# mapleCUx_large_085-MAPLE-unten.net
KiCad netlist of a schematic drawn in EAGLE
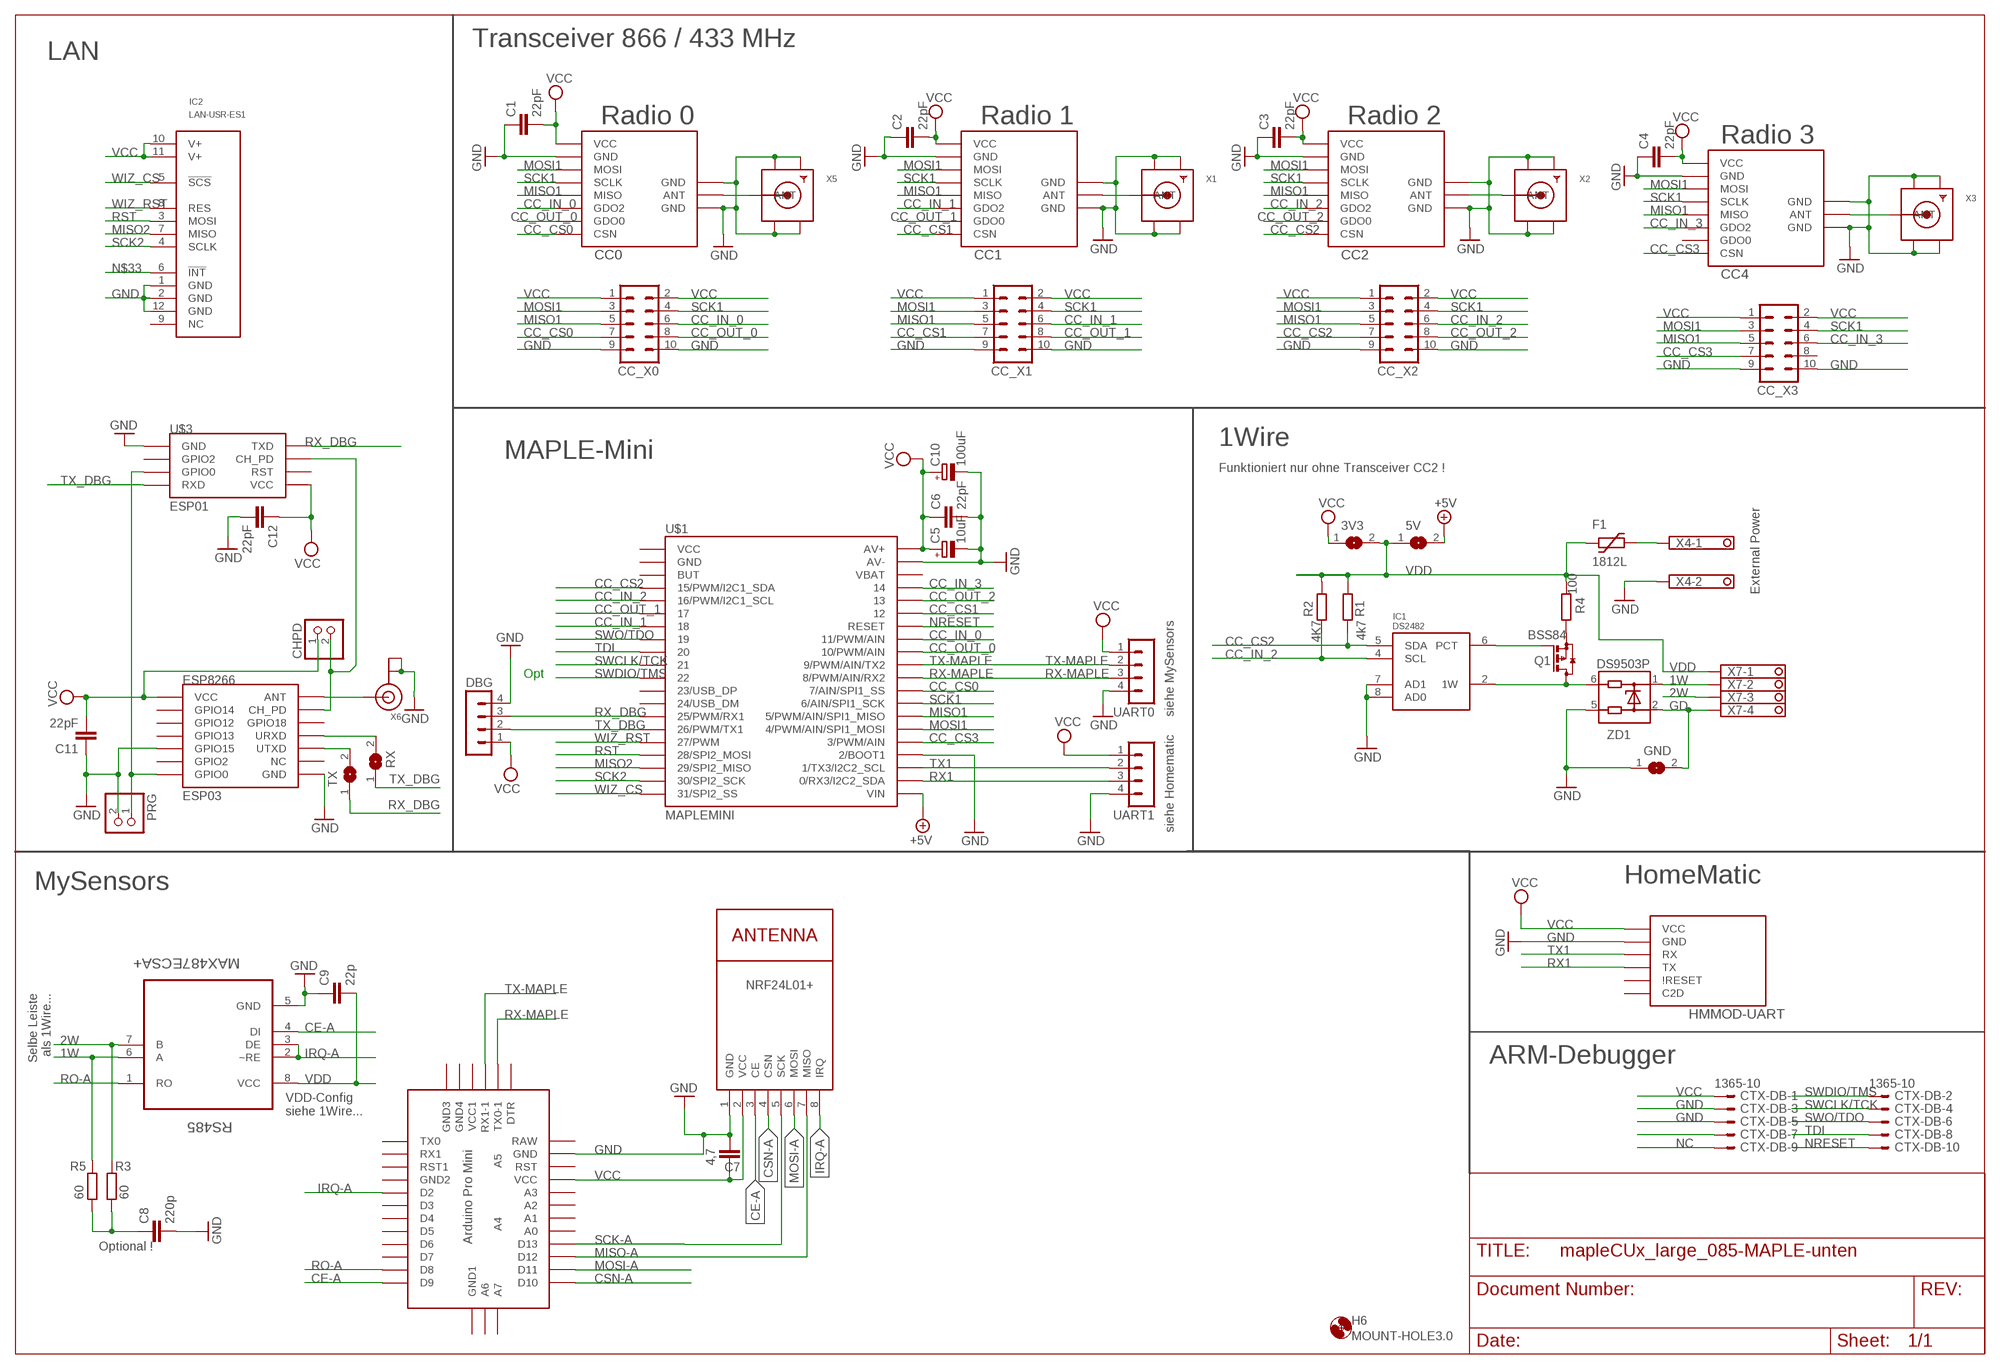
[diagram p0: schematic, sheet 1]

(export (version "E")
  (design (tool "Eeschema 10.0.6"))
  (components
    (comp (ref "3V3") (value "SJ") (footprint "eagle-import:SJ") (libsource (lib "eagle-import") (part "SJ")))
    (comp (ref "5V") (value "SJ") (footprint "eagle-import:SJ") (libsource (lib "eagle-import") (part "SJ")))
    (comp (ref "C1")
      (value "22pF")
      (footprint "eagle-import:C0805")
      (libsource (lib "eagle-import") (part "C-EUC0805"))
    )
    (comp (ref "C2")
      (value "22pF")
      (footprint "eagle-import:C0805")
      (libsource (lib "eagle-import") (part "C-EUC0805"))
    )
    (comp (ref "C3")
      (value "22pF")
      (footprint "eagle-import:C0805")
      (libsource (lib "eagle-import") (part "C-EUC0805"))
    )
    (comp (ref "C4")
      (value "22pF")
      (footprint "eagle-import:C0805")
      (libsource (lib "eagle-import") (part "C-EUC0805"))
    )
    (comp (ref "C5")
      (value "10uF")
      (footprint "eagle-import:R_2012-12W")
      (libsource (lib "eagle-import") (part "CPOL-EUR/2012-12W"))
    )
    (comp (ref "C6")
      (value "22pF")
      (footprint "eagle-import:C0805")
      (libsource (lib "eagle-import") (part "C-EUC0805"))
    )
    (comp (ref "C7")
      (value "4,7")
      (footprint "eagle-import:C1210")
      (libsource (lib "eagle-import") (part "C-EUC1210"))
    )
    (comp (ref "C8")
      (value "220p")
      (footprint "eagle-import:C0805")
      (libsource (lib "eagle-import") (part "C-EUC0805"))
    )
    (comp (ref "C9")
      (value "22p")
      (footprint "eagle-import:C0805")
      (libsource (lib "eagle-import") (part "C-EUC0805"))
    )
    (comp (ref "C10")
      (value "100uF")
      (footprint "eagle-import:E5-8,5")
      (libsource (lib "eagle-import") (part "CPOL-EUE5-8.5"))
    )
    (comp (ref "C11")
      (value "22pF")
      (footprint "eagle-import:C0805")
      (libsource (lib "eagle-import") (part "C-EUC0805"))
    )
    (comp (ref "C12")
      (value "22pF")
      (footprint "eagle-import:C0805")
      (libsource (lib "eagle-import") (part "C-EUC0805"))
    )
    (comp (ref "CC0")
      (value "CC1101")
      (footprint "eagle-import:CC1101_MODULE1_SMD")
      (libsource (lib "eagle-import") (part "CC1101_MODULE1SMD"))
    )
    (comp (ref "CC1")
      (value "CC1101_MODULE1SMD")
      (footprint "eagle-import:CC1101_MODULE1_SMD")
      (libsource (lib "eagle-import") (part "CC1101_MODULE1SMD"))
    )
    (comp (ref "CC2")
      (value "CC1101_MODULE1SMD")
      (footprint "eagle-import:CC1101_MODULE1_SMD")
      (libsource (lib "eagle-import") (part "CC1101_MODULE1SMD"))
    )
    (comp (ref "CC4")
      (value "CC1101_MODULE1SMD")
      (footprint "eagle-import:CC1101_MODULE1_SMD")
      (libsource (lib "eagle-import") (part "CC1101_MODULE1SMD"))
    )
    (comp (ref "CC_X0")
      (value "MA05-2")
      (footprint "eagle-import:MA05-2")
      (libsource (lib "eagle-import") (part "MA05-2"))
    )
    (comp (ref "CC_X1")
      (value "MA05-2")
      (footprint "eagle-import:MA05-2")
      (libsource (lib "eagle-import") (part "MA05-2"))
    )
    (comp (ref "CC_X2")
      (value "MA05-2")
      (footprint "eagle-import:MA05-2")
      (libsource (lib "eagle-import") (part "MA05-2"))
    )
    (comp (ref "CC_X3")
      (value "MA05-2")
      (footprint "eagle-import:MA05-2")
      (libsource (lib "eagle-import") (part "MA05-2"))
    )
    (comp (ref "CHPD")
      (value "PINHD-1X2")
      (footprint "eagle-import:1X02")
      (libsource (lib "eagle-import") (part "PINHD-1X2"))
    )
    (comp (ref "CTX-DB")
      (value "1365-10")
      (footprint "eagle-import:1365-10")
      (libsource (lib "eagle-import") (part "1365-10"))
    )
    (comp (ref "DBG")
      (value "MA04-1")
      (footprint "eagle-import:MA04-1")
      (libsource (lib "eagle-import") (part "MA04-1"))
    )
    (comp (ref "ESP8266")
      (value "ESP03")
      (footprint "eagle-import:ESP03")
      (libsource (lib "eagle-import") (part "ESP03"))
    )
    (comp (ref "F1")
      (value "1812L")
      (footprint "eagle-import:1812L")
      (libsource (lib "eagle-import") (part "1812L"))
    )
    (comp (ref "GND") (value "SJ") (footprint "eagle-import:SJ") (libsource (lib "eagle-import") (part "SJ")))
    (comp (ref "H6")
      (value "MOUNT-HOLE3.0")
      (footprint "eagle-import:3,0")
      (libsource (lib "eagle-import") (part "MOUNT-HOLE3.0"))
    )
    (comp (ref "HMMOD-UART")
      (value "HM-MOD-UARTDIL")
      (footprint "eagle-import:HM-MOD-UART-DIL")
      (libsource (lib "eagle-import") (part "HM-MOD-UARTDIL"))
    )
    (comp (ref "IC1")
      (value "DS2482")
      (footprint "eagle-import:SO08")
      (libsource (lib "eagle-import") (part "DS2482-100S"))
    )
    (comp (ref "IC2")
      (value "LAN-USR-ES1")
      (footprint "eagle-import:USR-ES1")
      (libsource (lib "eagle-import") (part "LAN-USR-ES1"))
    )
    (comp (ref "NRF24L01+")
      (value "NRF24L01+")
      (footprint "eagle-import:WIRELESS-NRF24L01")
      (libsource (lib "eagle-import") (part "WIRELESS-NRF24L01"))
    )
    (comp (ref "PRG")
      (value "PINHD-1X2")
      (footprint "eagle-import:1X02")
      (libsource (lib "eagle-import") (part "PINHD-1X2"))
    )
    (comp (ref "Q1")
      (value "BSS84")
      (footprint "eagle-import:SOT23")
      (libsource (lib "eagle-import") (part "BSS84"))
    )
    (comp (ref "R1")
      (value "4k7")
      (footprint "eagle-import:R0805")
      (libsource (lib "eagle-import") (part "R-EU_R0805"))
    )
    (comp (ref "R2")
      (value "4K7")
      (footprint "eagle-import:R0805")
      (libsource (lib "eagle-import") (part "R-EU_R0805"))
    )
    (comp (ref "R3")
      (value "60")
      (footprint "eagle-import:R0805")
      (libsource (lib "eagle-import") (part "R-EU_R0805"))
    )
    (comp (ref "R4")
      (value "100")
      (footprint "eagle-import:R0805")
      (libsource (lib "eagle-import") (part "R-EU_R0805"))
    )
    (comp (ref "R5")
      (value "60")
      (footprint "eagle-import:R0805")
      (libsource (lib "eagle-import") (part "R-EU_R0805"))
    )
    (comp (ref "RS485")
      (value "MAX487ECSA+")
      (footprint "eagle-import:SOIC127P600X175-8N")
      (libsource (lib "eagle-import") (part "MAX487ECSA+"))
    )
    (comp (ref "RX") (value "SJ") (footprint "eagle-import:SJ") (libsource (lib "eagle-import") (part "SJ")))
    (comp (ref "TX") (value "SJ") (footprint "eagle-import:SJ") (libsource (lib "eagle-import") (part "SJ")))
    (comp (ref "U$1")
      (value "MAPLEMINI")
      (footprint "eagle-import:20-DIP")
      (libsource (lib "eagle-import") (part "MAPLEMINI"))
    )
    (comp (ref "U$2")
      (value "ABK-PRO-MINI")
      (footprint "eagle-import:ABK-PRO-MINI")
      (libsource (lib "eagle-import") (part "ABK-PRO-MINI"))
    )
    (comp (ref "U$3")
      (value "ESP01")
      (footprint "eagle-import:ESP01")
      (libsource (lib "eagle-import") (part "ESP01"))
    )
    (comp (ref "UART0")
      (value "MA04-1")
      (footprint "eagle-import:MA04-1")
      (libsource (lib "eagle-import") (part "MA04-1"))
    )
    (comp (ref "UART1")
      (value "MA04-1")
      (footprint "eagle-import:MA04-1")
      (libsource (lib "eagle-import") (part "MA04-1"))
    )
    (comp (ref "X1")
      (value "SMACONNECTOR_EDGE_UFL")
      (footprint "eagle-import:SMA_EDGELAUNCH_UFL")
      (libsource (lib "eagle-import") (part "SMACONNECTOR_EDGE_UFL"))
    )
    (comp (ref "X2")
      (value "SMACONNECTOR_EDGE_UFL")
      (footprint "eagle-import:SMA_EDGELAUNCH_UFL")
      (libsource (lib "eagle-import") (part "SMACONNECTOR_EDGE_UFL"))
    )
    (comp (ref "X3")
      (value "SMACONNECTOR_EDGE_UFL")
      (footprint "eagle-import:SMA_EDGELAUNCH_UFL")
      (libsource (lib "eagle-import") (part "SMACONNECTOR_EDGE_UFL"))
    )
    (comp (ref "X4")
      (value "1751248")
      (footprint "eagle-import:1751248")
      (libsource (lib "eagle-import") (part "1751248"))
    )
    (comp (ref "X5")
      (value "SMACONNECTOR_EDGE_UFL")
      (footprint "eagle-import:SMA_EDGELAUNCH_UFL")
      (libsource (lib "eagle-import") (part "SMACONNECTOR_EDGE_UFL"))
    )
    (comp (ref "X6")
      (value "ANTENNA_U.FL")
      (footprint "eagle-import:U.FL")
      (libsource (lib "eagle-import") (part "ANTENNA_U.FL"))
    )
    (comp (ref "X7")
      (value "1751264")
      (footprint "eagle-import:1751264")
      (libsource (lib "eagle-import") (part "1751264"))
    )
    (comp (ref "ZD1")
      (value "DS9503P")
      (footprint "eagle-import:TSOC6")
      (libsource (lib "eagle-import") (part "DS9503P"))
    )
  )
  (nets
    (net (code "1") (name "+5V") (class "Default")
      (node (ref "5V") (pin "2") (pinfunction "2_2") (pintype "passive"))
      (node (ref "U$1") (pin "21") (pinfunction "VIN_21") (pintype "bidirectional"))
    )
    (net (code "2") (name "/1W") (class "Default")
      (node (ref "R5") (pin "2") (pinfunction "2_2") (pintype "passive"))
      (node (ref "RS485") (pin "6") (pinfunction "A_6") (pintype "bidirectional"))
      (node (ref "X7") (pin "2") (pinfunction "K_2") (pintype "passive"))
      (node (ref "ZD1") (pin "1") (pinfunction "P$1_1") (pintype "passive"))
    )
    (net (code "3") (name "/2W") (class "Default")
      (node (ref "R3") (pin "2") (pinfunction "2_2") (pintype "passive"))
      (node (ref "RS485") (pin "7") (pinfunction "B_7") (pintype "bidirectional"))
      (node (ref "X7") (pin "3") (pinfunction "K_3") (pintype "passive"))
    )
    (net (code "4") (name "/CC_CS0") (class "Default")
      (node (ref "CC0") (pin "CSN") (pinfunction "CSN_CSN") (pintype "bidirectional"))
      (node (ref "CC_X0") (pin "7") (pinfunction "7_7") (pintype "passive"))
      (node (ref "U$1") (pin "29") (pinfunction "7/AIN/SPI1_SS_29") (pintype "bidirectional"))
    )
    (net (code "5") (name "/CC_CS1") (class "Default")
      (node (ref "CC1") (pin "CSN") (pinfunction "CSN_CSN") (pintype "bidirectional"))
      (node (ref "CC_X1") (pin "7") (pinfunction "7_7") (pintype "passive"))
      (node (ref "U$1") (pin "35") (pinfunction "12_35") (pintype "bidirectional"))
    )
    (net (code "6") (name "/CC_CS2") (class "Default")
      (node (ref "CC2") (pin "CSN") (pinfunction "CSN_CSN") (pintype "bidirectional"))
      (node (ref "CC_X2") (pin "7") (pinfunction "7_7") (pintype "passive"))
      (node (ref "IC1") (pin "5") (pinfunction "SDA_5") (pintype "bidirectional"))
      (node (ref "R1") (pin "2") (pinfunction "2_2") (pintype "passive"))
      (node (ref "U$1") (pin "4") (pinfunction "15/PWM/I2C1_SDA_4") (pintype "bidirectional"))
    )
    (net (code "7") (name "/CC_CS3") (class "Default")
      (node (ref "CC4") (pin "CSN") (pinfunction "CSN_CSN") (pintype "bidirectional"))
      (node (ref "CC_X3") (pin "7") (pinfunction "7_7") (pintype "passive"))
      (node (ref "U$1") (pin "25") (pinfunction "3/PWM/AIN_25") (pintype "bidirectional"))
    )
    (net (code "8") (name "/CC_IN_0") (class "Default")
      (node (ref "CC0") (pin "GDO2") (pinfunction "GDO2_GDO2") (pintype "bidirectional"))
      (node (ref "CC_X0") (pin "6") (pinfunction "6_6") (pintype "passive"))
      (node (ref "U$1") (pin "33") (pinfunction "11/PWM/AIN_33") (pintype "bidirectional"))
    )
    (net (code "9") (name "/CC_IN_1") (class "Default")
      (node (ref "CC1") (pin "GDO2") (pinfunction "GDO2_GDO2") (pintype "bidirectional"))
      (node (ref "CC_X1") (pin "6") (pinfunction "6_6") (pintype "passive"))
      (node (ref "U$1") (pin "7") (pinfunction "18_7") (pintype "bidirectional"))
    )
    (net (code "10") (name "/CC_IN_2") (class "Default")
      (node (ref "CC2") (pin "GDO2") (pinfunction "GDO2_GDO2") (pintype "bidirectional"))
      (node (ref "CC_X2") (pin "6") (pinfunction "6_6") (pintype "passive"))
      (node (ref "IC1") (pin "4") (pinfunction "SCL_4") (pintype "input"))
      (node (ref "R2") (pin "2") (pinfunction "2_2") (pintype "passive"))
      (node (ref "U$1") (pin "5") (pinfunction "16/PWM/I2C1_SCL_5") (pintype "bidirectional"))
    )
    (net (code "11") (name "/CC_IN_3") (class "Default")
      (node (ref "CC4") (pin "GDO2") (pinfunction "GDO2_GDO2") (pintype "bidirectional"))
      (node (ref "CC_X3") (pin "6") (pinfunction "6_6") (pintype "passive"))
      (node (ref "U$1") (pin "37") (pinfunction "14_37") (pintype "bidirectional"))
    )
    (net (code "12") (name "/CC_OUT_0") (class "Default")
      (node (ref "CC0") (pin "GDO0") (pinfunction "GDO0_GDO0") (pintype "bidirectional"))
      (node (ref "CC_X0") (pin "8") (pinfunction "8_8") (pintype "passive"))
      (node (ref "U$1") (pin "32") (pinfunction "10/PWM/AIN_32") (pintype "bidirectional"))
    )
    (net (code "13") (name "/CC_OUT_1") (class "Default")
      (node (ref "CC1") (pin "GDO0") (pinfunction "GDO0_GDO0") (pintype "bidirectional"))
      (node (ref "CC_X1") (pin "8") (pinfunction "8_8") (pintype "passive"))
      (node (ref "U$1") (pin "6") (pinfunction "17_6") (pintype "bidirectional"))
    )
    (net (code "14") (name "/CC_OUT_2") (class "Default")
      (node (ref "CC2") (pin "GDO0") (pinfunction "GDO0_GDO0") (pintype "bidirectional"))
      (node (ref "CC_X2") (pin "8") (pinfunction "8_8") (pintype "passive"))
      (node (ref "U$1") (pin "36") (pinfunction "13_36") (pintype "bidirectional"))
    )
    (net (code "15") (name "/GD") (class "Default")
      (node (ref "GND") (pin "2") (pinfunction "2_2") (pintype "passive"))
      (node (ref "X7") (pin "4") (pinfunction "K_4") (pintype "passive"))
      (node (ref "ZD1") (pin "2") (pinfunction "P$2_2") (pintype "passive"))
    )
    (net (code "16") (name "/MISO-A") (class "Default")
      (node (ref "NRF24L01+") (pin "7") (pinfunction "MISO_7") (pintype "bidirectional"))
      (node (ref "U$2") (pin "D12") (pinfunction "D12_D12") (pintype "bidirectional"))
    )
    (net (code "17") (name "/MISO1") (class "Default")
      (node (ref "CC0") (pin "MISO") (pinfunction "MISO_MISO") (pintype "bidirectional"))
      (node (ref "CC1") (pin "MISO") (pinfunction "MISO_MISO") (pintype "bidirectional"))
      (node (ref "CC2") (pin "MISO") (pinfunction "MISO_MISO") (pintype "bidirectional"))
      (node (ref "CC4") (pin "MISO") (pinfunction "MISO_MISO") (pintype "bidirectional"))
      (node (ref "CC_X0") (pin "5") (pinfunction "5_5") (pintype "passive"))
      (node (ref "CC_X1") (pin "5") (pinfunction "5_5") (pintype "passive"))
      (node (ref "CC_X2") (pin "5") (pinfunction "5_5") (pintype "passive"))
      (node (ref "CC_X3") (pin "5") (pinfunction "5_5") (pintype "passive"))
      (node (ref "U$1") (pin "27") (pinfunction "5/PWM/AIN/SPI1_MISO_27") (pintype "bidirectional"))
    )
    (net (code "18") (name "/MISO2") (class "Default")
      (node (ref "IC2") (pin "7") (pinfunction "MISO_7") (pintype "bidirectional"))
      (node (ref "U$1") (pin "18") (pinfunction "29/SPI2_MISO_18") (pintype "bidirectional"))
    )
    (net (code "19") (name "/MOSI1") (class "Default")
      (node (ref "CC0") (pin "MOSI") (pinfunction "MOSI_MOSI") (pintype "bidirectional"))
      (node (ref "CC1") (pin "MOSI") (pinfunction "MOSI_MOSI") (pintype "bidirectional"))
      (node (ref "CC2") (pin "MOSI") (pinfunction "MOSI_MOSI") (pintype "bidirectional"))
      (node (ref "CC4") (pin "MOSI") (pinfunction "MOSI_MOSI") (pintype "bidirectional"))
      (node (ref "CC_X0") (pin "3") (pinfunction "3_3") (pintype "passive"))
      (node (ref "CC_X1") (pin "3") (pinfunction "3_3") (pintype "passive"))
      (node (ref "CC_X2") (pin "3") (pinfunction "3_3") (pintype "passive"))
      (node (ref "CC_X3") (pin "3") (pinfunction "3_3") (pintype "passive"))
      (node (ref "U$1") (pin "26") (pinfunction "4/PWM/AIN/SPI1_MOSI_26") (pintype "bidirectional"))
    )
    (net (code "20") (name "/N$33") (class "Default")
      (node (ref "IC2") (pin "6") (pinfunction "~{INT}_6") (pintype "output"))
    )
    (net (code "21") (name "/NC") (class "Default")
      (node (ref "CTX-DB") (pin "9") (pinfunction "S_9") (pintype "passive"))
    )
    (net (code "22") (name "/NRESET") (class "Default")
      (node (ref "CTX-DB") (pin "10") (pinfunction "S_10") (pintype "passive"))
      (node (ref "U$1") (pin "34") (pinfunction "RESET_34") (pintype "bidirectional"))
    )
    (net (code "23") (name "/RO-A") (class "Default")
      (node (ref "RS485") (pin "1") (pinfunction "RO_1") (pintype "output"))
      (node (ref "U$2") (pin "D8") (pinfunction "D8_D8") (pintype "bidirectional"))
    )
    (net (code "24") (name "/RST") (class "Default")
      (node (ref "IC2") (pin "3") (pinfunction "MOSI_3") (pintype "bidirectional"))
      (node (ref "U$1") (pin "17") (pinfunction "28/SPI2_MOSI_17") (pintype "bidirectional"))
    )
    (net (code "25") (name "/RX-MAPLE") (class "Default")
      (node (ref "U$1") (pin "30") (pinfunction "8/PWM/AIN/RX2_30") (pintype "bidirectional"))
      (node (ref "U$2") (pin "TX0-1") (pinfunction "TX0-1_TX0-1") (pintype "bidirectional"))
      (node (ref "UART0") (pin "3") (pinfunction "3_3") (pintype "passive"))
    )
    (net (code "26") (name "/RX1") (class "Default")
      (node (ref "HMMOD-UART") (pin "5") (pinfunction "TX_5") (pintype "bidirectional"))
      (node (ref "U$1") (pin "22") (pinfunction "0/RX3/I2C2_SDA_22") (pintype "bidirectional"))
      (node (ref "UART1") (pin "3") (pinfunction "3_3") (pintype "passive"))
    )
    (net (code "27") (name "/RX_DBG") (class "Default")
      (node (ref "DBG") (pin "3") (pinfunction "3_3") (pintype "passive"))
      (node (ref "TX") (pin "1") (pinfunction "1_1") (pintype "passive"))
      (node (ref "U$1") (pin "14") (pinfunction "25/PWM/RX1_14") (pintype "bidirectional"))
      (node (ref "U$3") (pin "TX") (pinfunction "TXD_TX") (pintype "bidirectional"))
    )
    (net (code "28") (name "/SCK-A") (class "Default")
      (node (ref "NRF24L01+") (pin "5") (pinfunction "SCK_5") (pintype "bidirectional"))
      (node (ref "U$2") (pin "D13") (pinfunction "D13_D13") (pintype "bidirectional"))
    )
    (net (code "29") (name "/SCK1") (class "Default")
      (node (ref "CC0") (pin "SCLK") (pinfunction "SCLK_SCLK") (pintype "bidirectional"))
      (node (ref "CC1") (pin "SCLK") (pinfunction "SCLK_SCLK") (pintype "bidirectional"))
      (node (ref "CC2") (pin "SCLK") (pinfunction "SCLK_SCLK") (pintype "bidirectional"))
      (node (ref "CC4") (pin "SCLK") (pinfunction "SCLK_SCLK") (pintype "bidirectional"))
      (node (ref "CC_X0") (pin "4") (pinfunction "4_4") (pintype "passive"))
      (node (ref "CC_X1") (pin "4") (pinfunction "4_4") (pintype "passive"))
      (node (ref "CC_X2") (pin "4") (pinfunction "4_4") (pintype "passive"))
      (node (ref "CC_X3") (pin "4") (pinfunction "4_4") (pintype "passive"))
      (node (ref "U$1") (pin "28") (pinfunction "6/AIN/SPI1_SCK_28") (pintype "bidirectional"))
    )
    (net (code "30") (name "/SCK2") (class "Default")
      (node (ref "IC2") (pin "4") (pinfunction "SCLK_4") (pintype "input"))
      (node (ref "U$1") (pin "19") (pinfunction "30/SPI2_SCK_19") (pintype "bidirectional"))
    )
    (net (code "31") (name "/SWCLK{slash}TCK") (class "Default")
      (node (ref "CTX-DB") (pin "4") (pinfunction "S_4") (pintype "passive"))
      (node (ref "U$1") (pin "10") (pinfunction "21_10") (pintype "bidirectional"))
    )
    (net (code "32") (name "/SWDIO{slash}TMS") (class "Default")
      (node (ref "CTX-DB") (pin "2") (pinfunction "S_2") (pintype "passive"))
      (node (ref "U$1") (pin "11") (pinfunction "22_11") (pintype "bidirectional"))
    )
    (net (code "33") (name "/SWO{slash}TDO") (class "Default")
      (node (ref "CTX-DB") (pin "6") (pinfunction "S_6") (pintype "passive"))
      (node (ref "U$1") (pin "8") (pinfunction "19_8") (pintype "bidirectional"))
    )
    (net (code "34") (name "/TDI") (class "Default")
      (node (ref "CTX-DB") (pin "8") (pinfunction "S_8") (pintype "passive"))
      (node (ref "U$1") (pin "9") (pinfunction "20_9") (pintype "bidirectional"))
    )
    (net (code "35") (name "/TX-MAPLE") (class "Default")
      (node (ref "U$1") (pin "31") (pinfunction "9/PWM/AIN/TX2_31") (pintype "bidirectional"))
      (node (ref "U$2") (pin "RX1-1") (pinfunction "RX1-1_RX1-1") (pintype "bidirectional"))
      (node (ref "UART0") (pin "2") (pinfunction "2_2") (pintype "passive"))
    )
    (net (code "36") (name "/TX1") (class "Default")
      (node (ref "HMMOD-UART") (pin "6") (pinfunction "RX_6") (pintype "bidirectional"))
      (node (ref "U$1") (pin "23") (pinfunction "1/TX3/I2C2_SCL_23") (pintype "bidirectional"))
      (node (ref "UART1") (pin "2") (pinfunction "2_2") (pintype "passive"))
    )
    (net (code "37") (name "/TX_DBG") (class "Default")
      (node (ref "DBG") (pin "2") (pinfunction "2_2") (pintype "passive"))
      (node (ref "RX") (pin "1") (pinfunction "1_1") (pintype "passive"))
      (node (ref "U$1") (pin "15") (pinfunction "26/PWM/TX1_15") (pintype "bidirectional"))
      (node (ref "U$3") (pin "RX") (pinfunction "RXD_RX") (pintype "bidirectional"))
    )
    (net (code "38") (name "/VDD") (class "Default")
      (node (ref "3V3") (pin "2") (pinfunction "2_2") (pintype "passive"))
      (node (ref "5V") (pin "1") (pinfunction "1_1") (pintype "passive"))
      (node (ref "C9") (pin "2") (pinfunction "2_2") (pintype "passive"))
      (node (ref "F1") (pin "P$1") (pinfunction "1_P$1") (pintype "passive"))
      (node (ref "R1") (pin "1") (pinfunction "1_1") (pintype "passive"))
      (node (ref "R2") (pin "1") (pinfunction "1_1") (pintype "passive"))
      (node (ref "R4") (pin "2") (pinfunction "2_2") (pintype "passive"))
      (node (ref "RS485") (pin "8") (pinfunction "VCC_8") (pintype "power_in"))
      (node (ref "X7") (pin "1") (pinfunction "K_1") (pintype "passive"))
    )
    (net (code "39") (name "/WIZ_CS") (class "Default")
      (node (ref "IC2") (pin "5") (pinfunction "~{SCS}_5") (pintype "input"))
      (node (ref "U$1") (pin "20") (pinfunction "31/SPI2_SS_20") (pintype "bidirectional"))
    )
    (net (code "40") (name "/WIZ_RST") (class "Default")
      (node (ref "IC2") (pin "8") (pinfunction "RES_8") (pintype "input"))
      (node (ref "U$1") (pin "16") (pinfunction "27/PWM_16") (pintype "bidirectional"))
    )
    (net (code "41") (name "CE-A") (class "Default")
      (node (ref "NRF24L01+") (pin "3") (pinfunction "CE_3") (pintype "bidirectional"))
      (node (ref "RS485") (pin "4") (pinfunction "DI_4") (pintype "input"))
      (node (ref "U$2") (pin "D9") (pinfunction "D9_D9") (pintype "bidirectional"))
    )
    (net (code "42") (name "CSN-A") (class "Default")
      (node (ref "NRF24L01+") (pin "4") (pinfunction "CSN_4") (pintype "bidirectional"))
      (node (ref "U$2") (pin "D10") (pinfunction "D10_D10") (pintype "bidirectional"))
    )
    (net (code "43") (name "GND") (class "Default")
      (node (ref "C1") (pin "1") (pinfunction "1_1") (pintype "passive"))
      (node (ref "C10") (pin "-") (pinfunction "-_-") (pintype "passive"))
      (node (ref "C11") (pin "1") (pinfunction "1_1") (pintype "passive"))
      (node (ref "C12") (pin "2") (pinfunction "2_2") (pintype "passive"))
      (node (ref "C2") (pin "1") (pinfunction "1_1") (pintype "passive"))
      (node (ref "C3") (pin "1") (pinfunction "1_1") (pintype "passive"))
      (node (ref "C4") (pin "1") (pinfunction "1_1") (pintype "passive"))
      (node (ref "C5") (pin "-") (pinfunction "-_-") (pintype "passive"))
      (node (ref "C6") (pin "2") (pinfunction "2_2") (pintype "passive"))
      (node (ref "C7") (pin "1") (pinfunction "1_1") (pintype "passive"))
      (node (ref "C8") (pin "2") (pinfunction "2_2") (pintype "passive"))
      (node (ref "C9") (pin "1") (pinfunction "1_1") (pintype "passive"))
      (node (ref "CC0") (pin "GND@0") (pinfunction "GND_GND@0") (pintype "power_in"))
      (node (ref "CC0") (pin "GND@1") (pinfunction "GND_GND@1") (pintype "power_in"))
      (node (ref "CC0") (pin "GND@2") (pinfunction "GND_GND@2") (pintype "power_in"))
      (node (ref "CC1") (pin "GND@0") (pinfunction "GND_GND@0") (pintype "power_in"))
      (node (ref "CC1") (pin "GND@1") (pinfunction "GND_GND@1") (pintype "power_in"))
      (node (ref "CC1") (pin "GND@2") (pinfunction "GND_GND@2") (pintype "power_in"))
      (node (ref "CC2") (pin "GND@0") (pinfunction "GND_GND@0") (pintype "power_in"))
      (node (ref "CC2") (pin "GND@1") (pinfunction "GND_GND@1") (pintype "power_in"))
      (node (ref "CC2") (pin "GND@2") (pinfunction "GND_GND@2") (pintype "power_in"))
      (node (ref "CC4") (pin "GND@0") (pinfunction "GND_GND@0") (pintype "power_in"))
      (node (ref "CC4") (pin "GND@1") (pinfunction "GND_GND@1") (pintype "power_in"))
      (node (ref "CC4") (pin "GND@2") (pinfunction "GND_GND@2") (pintype "power_in"))
      (node (ref "CC_X0") (pin "10") (pinfunction "10_10") (pintype "passive"))
      (node (ref "CC_X0") (pin "9") (pinfunction "9_9") (pintype "passive"))
      (node (ref "CC_X1") (pin "10") (pinfunction "10_10") (pintype "passive"))
      (node (ref "CC_X1") (pin "9") (pinfunction "9_9") (pintype "passive"))
      (node (ref "CC_X2") (pin "10") (pinfunction "10_10") (pintype "passive"))
      (node (ref "CC_X2") (pin "9") (pinfunction "9_9") (pintype "passive"))
      (node (ref "CC_X3") (pin "10") (pinfunction "10_10") (pintype "passive"))
      (node (ref "CC_X3") (pin "9") (pinfunction "9_9") (pintype "passive"))
      (node (ref "CTX-DB") (pin "3") (pinfunction "S_3") (pintype "passive"))
      (node (ref "CTX-DB") (pin "5") (pinfunction "S_5") (pintype "passive"))
      (node (ref "DBG") (pin "4") (pinfunction "4_4") (pintype "passive"))
      (node (ref "ESP8266") (pin "GND") (pinfunction "GND_GND") (pintype "bidirectional"))
      (node (ref "ESP8266") (pin "GPIO15") (pinfunction "GPIO15_GPIO15") (pintype "bidirectional"))
      (node (ref "GND") (pin "1") (pinfunction "1_1") (pintype "passive"))
      (node (ref "HMMOD-UART") (pin "2") (pinfunction "GND_2") (pintype "power_in"))
      (node (ref "IC1") (pin "7") (pinfunction "AD1_7") (pintype "input"))
      (node (ref "IC1") (pin "8") (pinfunction "AD0_8") (pintype "input"))
      (node (ref "IC2") (pin "1") (pinfunction "GND_1") (pintype "power_in"))
      (node (ref "IC2") (pin "12") (pinfunction "GND_12") (pintype "power_in"))
      (node (ref "IC2") (pin "2") (pinfunction "GND_2") (pintype "power_in"))
      (node (ref "NRF24L01+") (pin "1") (pinfunction "GND_1") (pintype "power_in"))
      (node (ref "PRG") (pin "2") (pinfunction "2_2") (pintype "passive"))
      (node (ref "RS485") (pin "5") (pinfunction "GND_5") (pintype "passive"))
      (node (ref "U$1") (pin "24") (pinfunction "2/BOOT1_24") (pintype "bidirectional"))
      (node (ref "U$1") (pin "39") (pinfunction "AV-_39") (pintype "bidirectional"))
      (node (ref "U$2") (pin "GND") (pinfunction "GND_GND") (pintype "bidirectional"))
      (node (ref "U$3") (pin "GND") (pinfunction "GND_GND") (pintype "bidirectional"))
      (node (ref "UART0") (pin "4") (pinfunction "4_4") (pintype "passive"))
      (node (ref "UART1") (pin "4") (pinfunction "4_4") (pintype "passive"))
      (node (ref "X1") (pin "GND@1") (pinfunction "GND1_GND@1") (pintype "power_in"))
      (node (ref "X1") (pin "GND@2") (pinfunction "GND2_GND@2") (pintype "power_in"))
      (node (ref "X1") (pin "GND@3") (pinfunction "GND3_GND@3") (pintype "power_in"))
      (node (ref "X1") (pin "GND@4") (pinfunction "GND4_GND@4") (pintype "power_in"))
      (node (ref "X2") (pin "GND@1") (pinfunction "GND1_GND@1") (pintype "power_in"))
      (node (ref "X2") (pin "GND@2") (pinfunction "GND2_GND@2") (pintype "power_in"))
      (node (ref "X2") (pin "GND@3") (pinfunction "GND3_GND@3") (pintype "power_in"))
      (node (ref "X2") (pin "GND@4") (pinfunction "GND4_GND@4") (pintype "power_in"))
      (node (ref "X3") (pin "GND@1") (pinfunction "GND1_GND@1") (pintype "power_in"))
      (node (ref "X3") (pin "GND@2") (pinfunction "GND2_GND@2") (pintype "power_in"))
      (node (ref "X3") (pin "GND@3") (pinfunction "GND3_GND@3") (pintype "power_in"))
      (node (ref "X3") (pin "GND@4") (pinfunction "GND4_GND@4") (pintype "power_in"))
      (node (ref "X4") (pin "2") (pinfunction "K_2") (pintype "passive"))
      (node (ref "X5") (pin "GND@1") (pinfunction "GND1_GND@1") (pintype "power_in"))
      (node (ref "X5") (pin "GND@2") (pinfunction "GND2_GND@2") (pintype "power_in"))
      (node (ref "X5") (pin "GND@3") (pinfunction "GND3_GND@3") (pintype "power_in"))
      (node (ref "X5") (pin "GND@4") (pinfunction "GND4_GND@4") (pintype "power_in"))
      (node (ref "X6") (pin "1") (pinfunction "GND_1") (pintype "passive"))
      (node (ref "X6") (pin "2") (pinfunction "GND_2") (pintype "passive"))
      (node (ref "ZD1") (pin "5") (pinfunction "P$3_5") (pintype "passive"))
    )
    (net (code "44") (name "IRQ-A") (class "Default")
      (node (ref "NRF24L01+") (pin "8") (pinfunction "IRQ_8") (pintype "bidirectional"))
      (node (ref "RS485") (pin "2") (pinfunction "~{RE}_2") (pintype "input"))
      (node (ref "RS485") (pin "3") (pinfunction "DE_3") (pintype "input"))
      (node (ref "U$2") (pin "D2") (pinfunction "D2_D2") (pintype "bidirectional"))
    )
    (net (code "45") (name "MOSI-A") (class "Default")
      (node (ref "NRF24L01+") (pin "6") (pinfunction "MOSI_6") (pintype "bidirectional"))
      (node (ref "U$2") (pin "D11") (pinfunction "D11_D11") (pintype "bidirectional"))
    )
    (net (code "46") (name "Net-(C8-Pad1)") (class "Default")
      (node (ref "C8") (pin "1") (pinfunction "1_1") (pintype "passive"))
      (node (ref "R3") (pin "1") (pinfunction "1_1") (pintype "passive"))
      (node (ref "R5") (pin "1") (pinfunction "1_1") (pintype "passive"))
    )
    (net (code "47") (name "Net-(CHPD-Pad2)") (class "Default")
      (node (ref "CHPD") (pin "2") (pinfunction "2_2") (pintype "passive"))
      (node (ref "ESP8266") (pin "CH_PD") (pinfunction "CH_PD_CH_PD") (pintype "bidirectional"))
      (node (ref "U$3") (pin "CH_PD") (pinfunction "CH_PD_CH_PD") (pintype "bidirectional"))
    )
    (net (code "48") (name "Net-(ESP8266-PadGPIO0)") (class "Default")
      (node (ref "ESP8266") (pin "GPIO0") (pinfunction "GPIO0_GPIO0") (pintype "bidirectional"))
      (node (ref "PRG") (pin "1") (pinfunction "1_1") (pintype "passive"))
      (node (ref "U$3") (pin "GPIO0") (pinfunction "GPIO0_GPIO0") (pintype "bidirectional"))
    )
    (net (code "49") (name "Net-(ESP8266-PadURXD)") (class "Default")
      (node (ref "ESP8266") (pin "URXD") (pinfunction "URXD_URXD") (pintype "bidirectional"))
      (node (ref "RX") (pin "2") (pinfunction "2_2") (pintype "passive"))
    )
    (net (code "50") (name "Net-(ESP8266-PadUTXD)") (class "Default")
      (node (ref "ESP8266") (pin "UTXD") (pinfunction "UTXD_UTXD") (pintype "bidirectional"))
      (node (ref "TX") (pin "2") (pinfunction "2_2") (pintype "passive"))
    )
    (net (code "51") (name "Net-(F1-2)") (class "Default")
      (node (ref "F1") (pin "P$2") (pinfunction "2_P$2") (pintype "passive"))
      (node (ref "X4") (pin "1") (pinfunction "K_1") (pintype "passive"))
    )
    (net (code "52") (name "Net-(IC1A-1W)") (class "Default")
      (node (ref "IC1") (pin "2") (pinfunction "1W_2") (pintype "open_collector"))
      (node (ref "Q1") (pin "3") (pinfunction "D_3") (pintype "passive"))
      (node (ref "ZD1") (pin "6") (pinfunction "P$4_6") (pintype "passive"))
    )
    (net (code "53") (name "Net-(IC1A-PCT)") (class "Default")
      (node (ref "IC1") (pin "6") (pinfunction "PCT_6") (pintype "output"))
      (node (ref "Q1") (pin "1") (pinfunction "G_1") (pintype "passive"))
    )
    (net (code "54") (name "Net-(Q1-S)") (class "Default")
      (node (ref "Q1") (pin "2") (pinfunction "S_2") (pintype "passive"))
      (node (ref "R4") (pin "1") (pinfunction "1_1") (pintype "passive"))
    )
    (net (code "55") (name "Net-(X1-ANT)") (class "Default")
      (node (ref "CC1") (pin "ANT") (pinfunction "ANT_ANT") (pintype "output"))
      (node (ref "X1") (pin "P") (pinfunction "ANT_P") (pintype "bidirectional"))
    )
    (net (code "56") (name "Net-(X2-ANT)") (class "Default")
      (node (ref "CC2") (pin "ANT") (pinfunction "ANT_ANT") (pintype "output"))
      (node (ref "X2") (pin "P") (pinfunction "ANT_P") (pintype "bidirectional"))
    )
    (net (code "57") (name "Net-(X3-ANT)") (class "Default")
      (node (ref "CC4") (pin "ANT") (pinfunction "ANT_ANT") (pintype "output"))
      (node (ref "X3") (pin "P") (pinfunction "ANT_P") (pintype "bidirectional"))
    )
    (net (code "58") (name "Net-(X5-ANT)") (class "Default")
      (node (ref "CC0") (pin "ANT") (pinfunction "ANT_ANT") (pintype "output"))
      (node (ref "X5") (pin "P") (pinfunction "ANT_P") (pintype "bidirectional"))
    )
    (net (code "59") (name "Net-(X6-SIGNAL)") (class "Default")
      (node (ref "ESP8266") (pin "ANT") (pinfunction "ANT_ANT") (pintype "bidirectional"))
      (node (ref "X6") (pin "3") (pinfunction "SIGNAL_3") (pintype "passive"))
    )
    (net (code "60") (name "VCC") (class "Default")
      (node (ref "3V3") (pin "1") (pinfunction "1_1") (pintype "passive"))
      (node (ref "C1") (pin "2") (pinfunction "2_2") (pintype "passive"))
      (node (ref "C10") (pin "+") (pinfunction "+_+") (pintype "passive"))
      (node (ref "C11") (pin "2") (pinfunction "2_2") (pintype "passive"))
      (node (ref "C12") (pin "1") (pinfunction "1_1") (pintype "passive"))
      (node (ref "C2") (pin "2") (pinfunction "2_2") (pintype "passive"))
      (node (ref "C3") (pin "2") (pinfunction "2_2") (pintype "passive"))
      (node (ref "C4") (pin "2") (pinfunction "2_2") (pintype "passive"))
      (node (ref "C5") (pin "+") (pinfunction "+_+") (pintype "passive"))
      (node (ref "C6") (pin "1") (pinfunction "1_1") (pintype "passive"))
      (node (ref "C7") (pin "2") (pinfunction "2_2") (pintype "passive"))
      (node (ref "CC0") (pin "VCC") (pinfunction "VCC_VCC") (pintype "power_in"))
      (node (ref "CC1") (pin "VCC") (pinfunction "VCC_VCC") (pintype "power_in"))
      (node (ref "CC2") (pin "VCC") (pinfunction "VCC_VCC") (pintype "power_in"))
      (node (ref "CC4") (pin "VCC") (pinfunction "VCC_VCC") (pintype "power_in"))
      (node (ref "CC_X0") (pin "1") (pinfunction "1_1") (pintype "passive"))
      (node (ref "CC_X0") (pin "2") (pinfunction "2_2") (pintype "passive"))
      (node (ref "CC_X1") (pin "1") (pinfunction "1_1") (pintype "passive"))
      (node (ref "CC_X1") (pin "2") (pinfunction "2_2") (pintype "passive"))
      (node (ref "CC_X2") (pin "1") (pinfunction "1_1") (pintype "passive"))
      (node (ref "CC_X2") (pin "2") (pinfunction "2_2") (pintype "passive"))
      (node (ref "CC_X3") (pin "1") (pinfunction "1_1") (pintype "passive"))
      (node (ref "CC_X3") (pin "2") (pinfunction "2_2") (pintype "passive"))
      (node (ref "CHPD") (pin "1") (pinfunction "1_1") (pintype "passive"))
      (node (ref "CTX-DB") (pin "1") (pinfunction "S_1") (pintype "passive"))
      (node (ref "DBG") (pin "1") (pinfunction "1_1") (pintype "passive"))
      (node (ref "ESP8266") (pin "VCC") (pinfunction "VCC_VCC") (pintype "bidirectional"))
      (node (ref "HMMOD-UART") (pin "1") (pinfunction "VCC_1") (pintype "power_in"))
      (node (ref "IC2") (pin "10") (pinfunction "V+_10") (pintype "power_in"))
      (node (ref "IC2") (pin "11") (pinfunction "V+_11") (pintype "power_in"))
      (node (ref "NRF24L01+") (pin "2") (pinfunction "VCC_2") (pintype "power_in"))
      (node (ref "U$1") (pin "40") (pinfunction "AV+_40") (pintype "bidirectional"))
      (node (ref "U$2") (pin "VCC") (pinfunction "VCC_VCC") (pintype "bidirectional"))
      (node (ref "U$3") (pin "VCC") (pinfunction "VCC_VCC") (pintype "bidirectional"))
      (node (ref "UART0") (pin "1") (pinfunction "1_1") (pintype "passive"))
      (node (ref "UART1") (pin "1") (pinfunction "1_1") (pintype "passive"))
    )
    (net (code "61") (name "unconnected-(CC4-PadGDO0)") (class "Default")
      (node (ref "CC4") (pin "GDO0") (pinfunction "GDO0_GDO0") (pintype "bidirectional"))
    )
    (net (code "62") (name "unconnected-(CC_X3-Pad8)") (class "Default")
      (node (ref "CC_X3") (pin "8") (pinfunction "8_8") (pintype "passive"))
    )
    (net (code "63") (name "unconnected-(CTX-DBH-S-Pad7)") (class "Default")
      (node (ref "CTX-DB") (pin "7") (pinfunction "S_7") (pintype "passive"))
    )
    (net (code "64") (name "unconnected-(ESP8266-PadGPIO2)") (class "Default")
      (node (ref "ESP8266") (pin "GPIO2") (pinfunction "GPIO2_GPIO2") (pintype "bidirectional"))
    )
    (net (code "65") (name "unconnected-(ESP8266-PadGPIO12)") (class "Default")
      (node (ref "ESP8266") (pin "GPIO12") (pinfunction "GPIO12_GPIO12") (pintype "bidirectional"))
    )
    (net (code "66") (name "unconnected-(ESP8266-PadGPIO13)") (class "Default")
      (node (ref "ESP8266") (pin "GPIO13") (pinfunction "GPIO13_GPIO13") (pintype "bidirectional"))
    )
    (net (code "67") (name "unconnected-(ESP8266-PadGPIO14)") (class "Default")
      (node (ref "ESP8266") (pin "GPIO14") (pinfunction "GPIO14_GPIO14") (pintype "bidirectional"))
    )
    (net (code "68") (name "unconnected-(ESP8266-PadGPIO18)") (class "Default")
      (node (ref "ESP8266") (pin "GPIO18") (pinfunction "GPIO18_GPIO18") (pintype "bidirectional"))
    )
    (net (code "69") (name "unconnected-(ESP8266-PadNC)") (class "Default")
      (node (ref "ESP8266") (pin "NC") (pinfunction "NC_NC") (pintype "bidirectional"))
    )
    (net (code "70") (name "unconnected-(HMMOD-UART-C2D-Pad3)") (class "Default")
      (node (ref "HMMOD-UART") (pin "3") (pinfunction "C2D_3") (pintype "bidirectional"))
    )
    (net (code "71") (name "unconnected-(HMMOD-UART-\\~{RESET}-Pad4)") (class "Default")
      (node (ref "HMMOD-UART") (pin "4") (pinfunction "\\~{RESET}_4") (pintype "bidirectional"))
    )
    (net (code "72") (name "unconnected-(IC2-NC-Pad9)") (class "Default")
      (node (ref "IC2") (pin "9") (pinfunction "NC_9") (pintype "no_connect"))
    )
    (net (code "73") (name "unconnected-(U$1-23{slash}USB_DP-Pad12)") (class "Default")
      (node (ref "U$1") (pin "12") (pinfunction "23/USB_DP_12") (pintype "bidirectional"))
    )
    (net (code "74") (name "unconnected-(U$1-24{slash}USB_DM-Pad13)") (class "Default")
      (node (ref "U$1") (pin "13") (pinfunction "24/USB_DM_13") (pintype "bidirectional"))
    )
    (net (code "75") (name "unconnected-(U$1-BUT-Pad3)") (class "Default")
      (node (ref "U$1") (pin "3") (pinfunction "BUT_3") (pintype "bidirectional"))
    )
    (net (code "76") (name "unconnected-(U$1-GND-Pad2)") (class "Default")
      (node (ref "U$1") (pin "2") (pinfunction "GND_2") (pintype "bidirectional"))
    )
    (net (code "77") (name "unconnected-(U$1-VBAT-Pad38)") (class "Default")
      (node (ref "U$1") (pin "38") (pinfunction "VBAT_38") (pintype "bidirectional"))
    )
    (net (code "78") (name "unconnected-(U$1-VCC-Pad1)") (class "Default")
      (node (ref "U$1") (pin "1") (pinfunction "VCC_1") (pintype "bidirectional"))
    )
    (net (code "79") (name "unconnected-(U$2-GND1-PadGND4)") (class "Default")
      (node (ref "U$2") (pin "GND4") (pinfunction "GND1_GND4") (pintype "bidirectional"))
    )
    (net (code "80") (name "unconnected-(U$2-GND2-PadGND1)") (class "Default")
      (node (ref "U$2") (pin "GND1") (pinfunction "GND2_GND1") (pintype "bidirectional"))
    )
    (net (code "81") (name "unconnected-(U$2-GND3-PadGND2)") (class "Default")
      (node (ref "U$2") (pin "GND2") (pinfunction "GND3_GND2") (pintype "bidirectional"))
    )
    (net (code "82") (name "unconnected-(U$2-GND4-PadGND3)") (class "Default")
      (node (ref "U$2") (pin "GND3") (pinfunction "GND4_GND3") (pintype "bidirectional"))
    )
    (net (code "83") (name "unconnected-(U$2-PadA0)") (class "Default")
      (node (ref "U$2") (pin "A0") (pinfunction "A0_A0") (pintype "bidirectional"))
    )
    (net (code "84") (name "unconnected-(U$2-PadA1)") (class "Default")
      (node (ref "U$2") (pin "A1") (pinfunction "A1_A1") (pintype "bidirectional"))
    )
    (net (code "85") (name "unconnected-(U$2-PadA2)") (class "Default")
      (node (ref "U$2") (pin "A2") (pinfunction "A2_A2") (pintype "bidirectional"))
    )
    (net (code "86") (name "unconnected-(U$2-PadA3)") (class "Default")
      (node (ref "U$2") (pin "A3") (pinfunction "A3_A3") (pintype "bidirectional"))
    )
    (net (code "87") (name "unconnected-(U$2-PadA4)") (class "Default")
      (node (ref "U$2") (pin "A4") (pinfunction "A4_A4") (pintype "bidirectional"))
    )
    (net (code "88") (name "unconnected-(U$2-PadA5)") (class "Default")
      (node (ref "U$2") (pin "A5") (pinfunction "A5_A5") (pintype "bidirectional"))
    )
    (net (code "89") (name "unconnected-(U$2-PadA6)") (class "Default")
      (node (ref "U$2") (pin "A6") (pinfunction "A6_A6") (pintype "bidirectional"))
    )
    (net (code "90") (name "unconnected-(U$2-PadA7)") (class "Default")
      (node (ref "U$2") (pin "A7") (pinfunction "A7_A7") (pintype "bidirectional"))
    )
    (net (code "91") (name "unconnected-(U$2-PadD3)") (class "Default")
      (node (ref "U$2") (pin "D3") (pinfunction "D3_D3") (pintype "bidirectional"))
    )
    (net (code "92") (name "unconnected-(U$2-PadD4)") (class "Default")
      (node (ref "U$2") (pin "D4") (pinfunction "D4_D4") (pintype "bidirectional"))
    )
    (net (code "93") (name "unconnected-(U$2-PadD5)") (class "Default")
      (node (ref "U$2") (pin "D5") (pinfunction "D5_D5") (pintype "bidirectional"))
    )
    (net (code "94") (name "unconnected-(U$2-PadD6)") (class "Default")
      (node (ref "U$2") (pin "D6") (pinfunction "D6_D6") (pintype "bidirectional"))
    )
    (net (code "95") (name "unconnected-(U$2-PadD7)") (class "Default")
      (node (ref "U$2") (pin "D7") (pinfunction "D7_D7") (pintype "bidirectional"))
    )
    (net (code "96") (name "unconnected-(U$2-PadDTR)") (class "Default")
      (node (ref "U$2") (pin "DTR") (pinfunction "DTR_DTR") (pintype "bidirectional"))
    )
    (net (code "97") (name "unconnected-(U$2-PadRAW)") (class "Default")
      (node (ref "U$2") (pin "RAW") (pinfunction "RAW_RAW") (pintype "bidirectional"))
    )
    (net (code "98") (name "unconnected-(U$2-PadRST)") (class "Default")
      (node (ref "U$2") (pin "RST") (pinfunction "RST_RST") (pintype "bidirectional"))
    )
    (net (code "99") (name "unconnected-(U$2-PadRST1)") (class "Default")
      (node (ref "U$2") (pin "RST1") (pinfunction "RST1_RST1") (pintype "bidirectional"))
    )
    (net (code "100") (name "unconnected-(U$2-PadRX1)") (class "Default")
      (node (ref "U$2") (pin "RX1") (pinfunction "RX1_RX1") (pintype "bidirectional"))
    )
    (net (code "101") (name "unconnected-(U$2-PadTX0)") (class "Default")
      (node (ref "U$2") (pin "TX0") (pinfunction "TX0_TX0") (pintype "bidirectional"))
    )
    (net (code "102") (name "unconnected-(U$2-PadVCC1)") (class "Default")
      (node (ref "U$2") (pin "VCC1") (pinfunction "VCC1_VCC1") (pintype "bidirectional"))
    )
    (net (code "103") (name "unconnected-(U$3-PadGPIO2)") (class "Default")
      (node (ref "U$3") (pin "GPIO2") (pinfunction "GPIO2_GPIO2") (pintype "bidirectional"))
    )
    (net (code "104") (name "unconnected-(U$3-PadRST)") (class "Default")
      (node (ref "U$3") (pin "RST") (pinfunction "RST_RST") (pintype "bidirectional"))
    )
  )
)
